# ottoesp_wrover.net
KiCad netlist of a schematic drawn in EAGLE
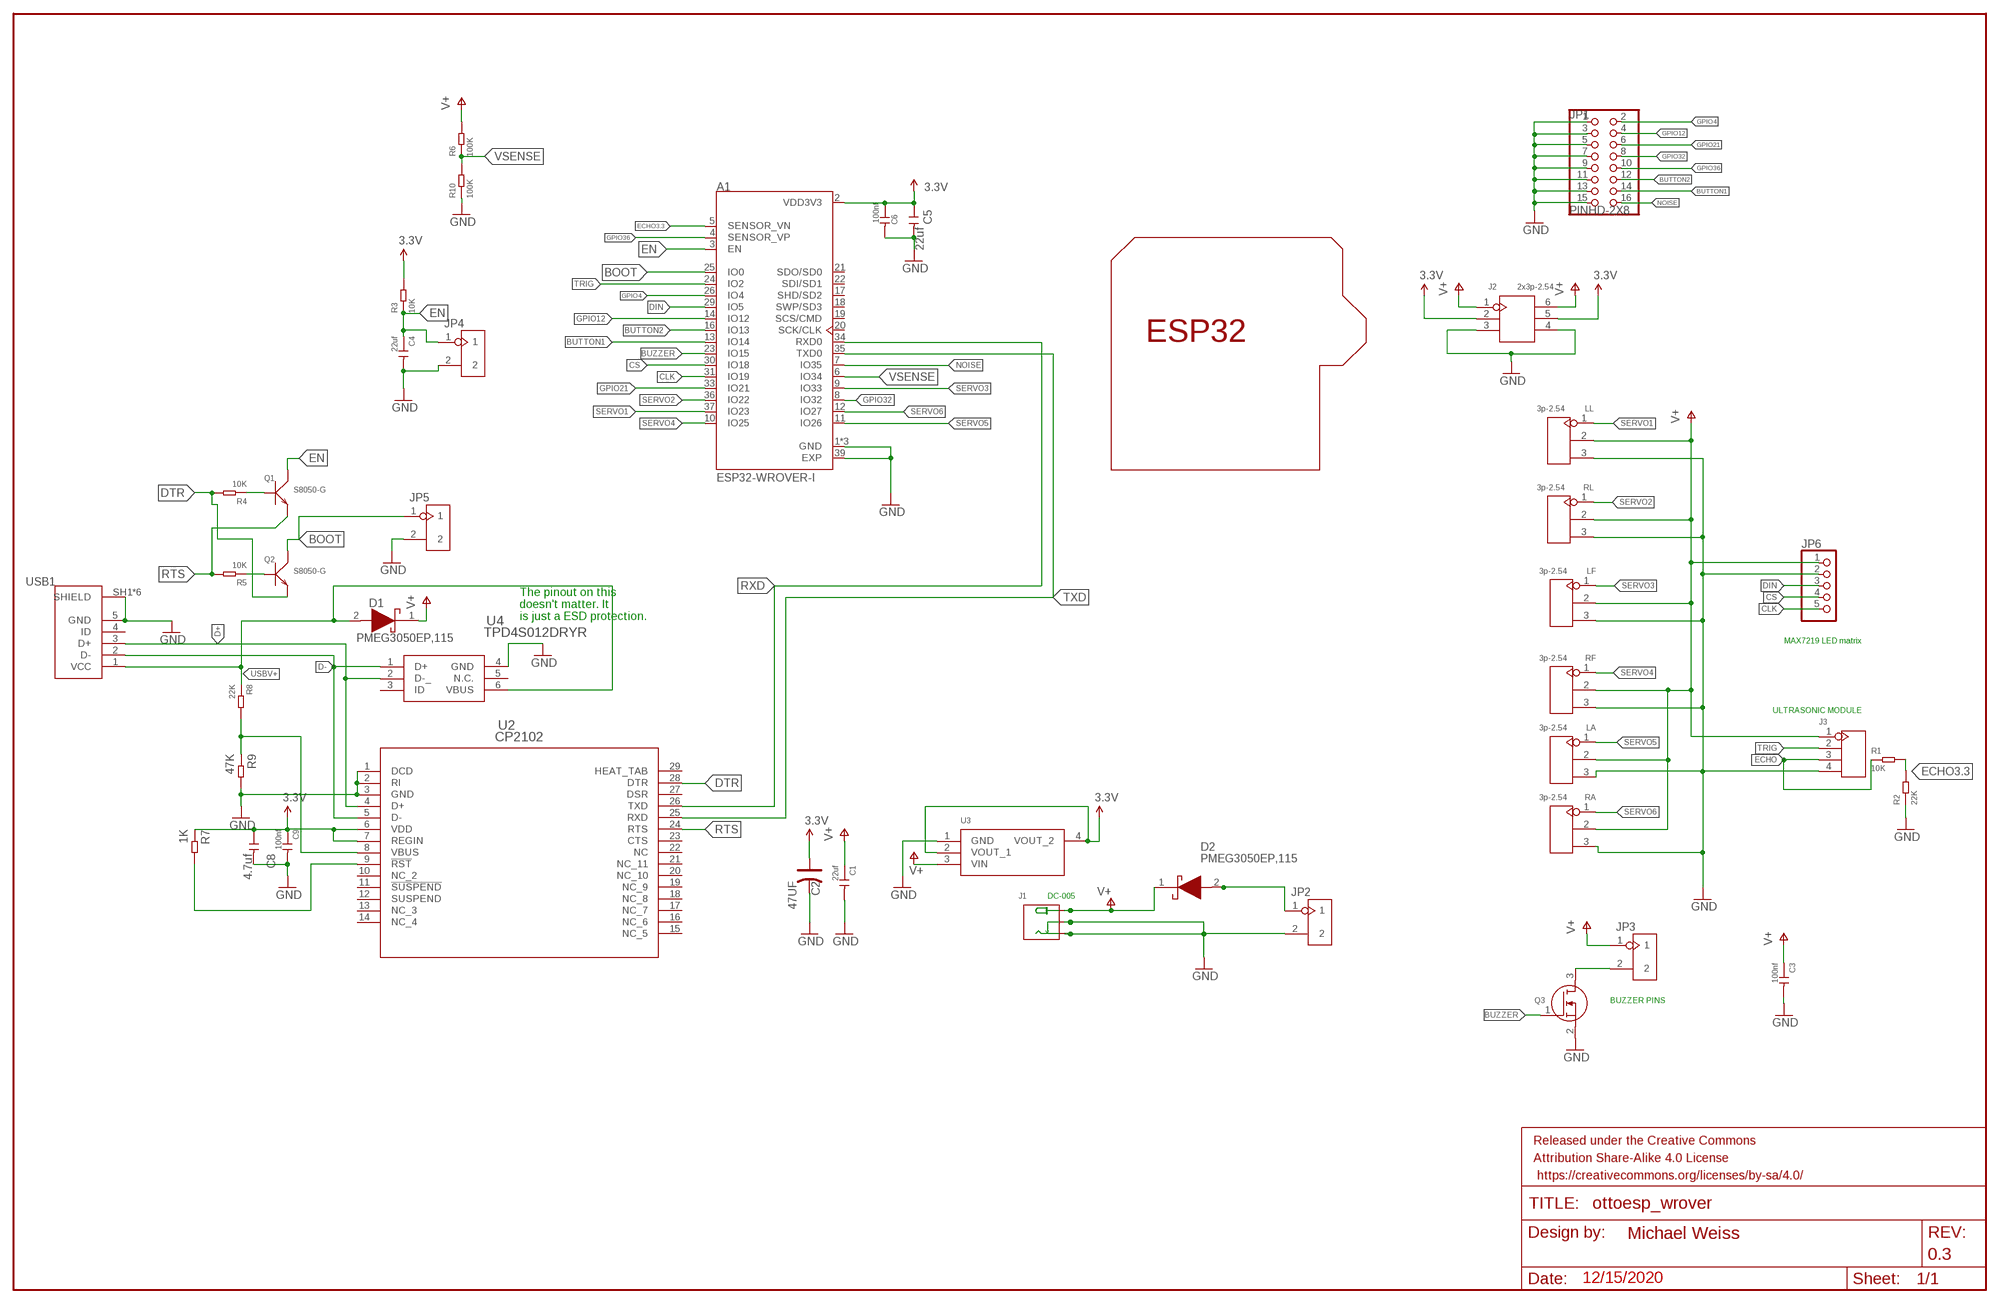
[diagram p0: schematic, sheet 1]

(export (version "E")
  (design (tool "Eeschema 10.0.6"))
  (components
    (comp (ref "A1")
      (value "ESP32-WROVER-I")
      (footprint "eagle-import:XCVR_ESP32-WROVER-I")
      (fields
        (field (name "MANUFACTURER_PART_NUMBER") "ESP32-WROVER-IE(M213EH2864UH3Q0) ")
        (field (name "MOUSER_PART_NUMBER") "356-ESP32WRVIE2864UC ")
      )
      (libsource (lib "eagle-import") (part "ESP32-WROVER-I"))
    )
    (comp (ref "C1")
      (value "22uf")
      (footprint "eagle-import:C0805")
      (fields
        (field (name "MANUFACTURER_PART_NUMBER") "C1206C226M9PACTU")
        (field (name "MOUSER_PART_NUMBER") "80-C1206C226M9P")
      )
      (libsource (lib "eagle-import") (part "CERAMIC-22UF-6.3V-20%-X5R(0805)"))
    )
    (comp (ref "C2")
      (value "47UF")
      (footprint "eagle-import:ELECTRO-SMD-C-6MM")
      (fields
        (field (name "MANUFACTURER_PART_NUMBER") " VE-470M1ETR-0605")
        (field (name "MOUSER_PART_NUMBER") "140-VE470M1ETR0605 ")
      )
      (libsource (lib "eagle-import") (part "ALUMINUM-SMD-47UF-25V(D6.3-H5.3MM)"))
    )
    (comp (ref "C3")
      (value "100nf")
      (footprint "eagle-import:C0805")
      (fields
        (field (name "MANUFACTURER_PART_NUMBER") "CC0805ZRY5V9BB104")
        (field (name "MOUSER_PART_NUMBER") "603-CC805ZRY5V9BB104")
      )
      (libsource (lib "eagle-import") (part "CERAMIC-100NF-50V-20%-X5R(0805)"))
    )
    (comp (ref "C4")
      (value "22uf")
      (footprint "eagle-import:C0805")
      (fields
        (field (name "MANUFACTURER_PART_NUMBER") "C1206C226M9PACTU")
        (field (name "MOUSER_PART_NUMBER") "80-C1206C226M9P")
      )
      (libsource (lib "eagle-import") (part "CERAMIC-22UF-6.3V-20%-X5R(0805)"))
    )
    (comp (ref "C5")
      (value "22uf")
      (footprint "eagle-import:C0805")
      (fields
        (field (name "MANUFACTURER_PART_NUMBER") "C1206C226M9PACTU")
        (field (name "MOUSER_PART_NUMBER") "80-C1206C226M9P")
      )
      (libsource (lib "eagle-import") (part "CERAMIC-22UF-6.3V-20%-X5R(0805)"))
    )
    (comp (ref "C6")
      (value "100nf")
      (footprint "eagle-import:C0805")
      (fields
        (field (name "MANUFACTURER_PART_NUMBER") "CC0805ZRY5V9BB104")
        (field (name "MOUSER_PART_NUMBER") "603-CC805ZRY5V9BB104")
      )
      (libsource (lib "eagle-import") (part "CERAMIC-100NF-50V-20%-X5R(0805)"))
    )
    (comp (ref "C8")
      (value "4.7uf")
      (footprint "eagle-import:C0805")
      (fields
        (field (name "MANUFACTURER_PART_NUMBER") "0805X475M250CT")
        (field (name "MOUSER_PART_NUMBER") "791-0805X475M250CT")
      )
      (libsource (lib "eagle-import") (part "CERAMIC-4.7UF-25V-10%-X5R(0805)"))
    )
    (comp (ref "C9")
      (value "100nf")
      (footprint "eagle-import:C0805")
      (fields
        (field (name "MANUFACTURER_PART_NUMBER") "CC0805ZRY5V9BB104")
        (field (name "MOUSER_PART_NUMBER") "603-CC805ZRY5V9BB104")
      )
      (libsource (lib "eagle-import") (part "CERAMIC-100NF-50V-20%-X5R(0805)"))
    )
    (comp (ref "D1")
      (value "PMEG3050EP,115")
      (footprint "eagle-import:PMEG3050EP115")
      (fields (field (name "MOUSER_PART_NUMBER") "771-PMEG3050EP115"))
      (libsource (lib "eagle-import") (part "PMEG3050EP,115"))
    )
    (comp (ref "D2")
      (value "PMEG3050EP,115")
      (footprint "eagle-import:PMEG3050EP115")
      (fields (field (name "MOUSER_PART_NUMBER") "771-PMEG3050EP115"))
      (libsource (lib "eagle-import") (part "PMEG3050EP,115"))
    )
    (comp (ref "FRAME1")
      (value "FRAME-LEDGERMISHAFARMS")
      (footprint "eagle-import:MISHAFARMS")
      (fields (field (name "DESIGNER") "Michael Weiss") (field (name "REV") "0.3"))
      (libsource (lib "eagle-import") (part "FRAME-LEDGERMISHAFARMS"))
    )
    (comp (ref "J1")
      (value "DC-005")
      (footprint "eagle-import:DCJ3P-14.2X11.0X9.0MM")
      (libsource (lib "eagle-import") (part "CONN-POWER-JACK-2.1MM(DC-005)"))
    )
    (comp (ref "J2")
      (value "2x3p-2.54")
      (footprint "eagle-import:H2X3-2.54")
      (fields (field (name "MANUFACTURER_PART_NUMBER") "P125-12A1BS116A1"))
      (libsource (lib "eagle-import") (part "DIP-BLACK-MALE-HEADER(2X3P-2.54）-2.54"))
    )
    (comp (ref "J3")
      (value "4p-2.54")
      (footprint "eagle-import:H4-2.54")
      (fields (field (name "MANUFACTURER_PART_NUMBER") "P125-1104A0BS116A1"))
      (libsource (lib "eagle-import") (part "DIP-BLACK-MALE-HEADER-VERT(4P-2.54)"))
    )
    (comp (ref "JP1")
      (value "PINHD-2X8")
      (footprint "eagle-import:2X08")
      (libsource (lib "eagle-import") (part "PINHD-2X8"))
    )
    (comp (ref "JP2")
      (value "2p-2.54")
      (footprint "eagle-import:H2-2.54")
      (fields (field (name "MANUFACTURER_PART_NUMBER") "P125-1102A0BS116A1"))
      (libsource (lib "eagle-import") (part "DIP-BLACK-MALE-HEADER-VERT(2P-2.54)"))
    )
    (comp (ref "JP3")
      (value "2p-2.54")
      (footprint "eagle-import:H2-2.54")
      (fields (field (name "MANUFACTURER_PART_NUMBER") "P125-1102A0BS116A1"))
      (libsource (lib "eagle-import") (part "DIP-BLACK-MALE-HEADER-VERT(2P-2.54)"))
    )
    (comp (ref "JP4")
      (value "2p-2.54")
      (footprint "eagle-import:H2-2.54")
      (fields (field (name "MANUFACTURER_PART_NUMBER") "P125-1102A0BS116A1"))
      (libsource (lib "eagle-import") (part "DIP-BLACK-MALE-HEADER-VERT(2P-2.54)"))
    )
    (comp (ref "JP5")
      (value "2p-2.54")
      (footprint "eagle-import:H2-2.54")
      (fields (field (name "MANUFACTURER_PART_NUMBER") "P125-1102A0BS116A1"))
      (libsource (lib "eagle-import") (part "DIP-BLACK-MALE-HEADER-VERT(2P-2.54)"))
    )
    (comp (ref "JP6")
      (value "PINHD-1X5")
      (footprint "eagle-import:1X05")
      (libsource (lib "eagle-import") (part "PINHD-1X5"))
    )
    (comp (ref "LA")
      (value "3p-2.54")
      (footprint "eagle-import:H3-2.54")
      (libsource (lib "eagle-import") (part "DIP-BLACK-MALE-HEADER-VERT(3P-2.54)"))
    )
    (comp (ref "LF")
      (value "3p-2.54")
      (footprint "eagle-import:H3-2.54")
      (libsource (lib "eagle-import") (part "DIP-BLACK-MALE-HEADER-VERT(3P-2.54)"))
    )
    (comp (ref "LL")
      (value "3p-2.54")
      (footprint "eagle-import:H3-2.54")
      (libsource (lib "eagle-import") (part "DIP-BLACK-MALE-HEADER-VERT(3P-2.54)"))
    )
    (comp (ref "Q1")
      (value "S8050-G")
      (footprint "eagle-import:SOT-23")
      (fields
        (field (name "MANUFACTURER_PART_NUMBER") "SS8050-G")
        (field (name "MOUSER_PART_NUMBER") "750-SS8050-G")
      )
      (libsource (lib "eagle-import") (part "SMD-TRANSISTORS-NPN-25V-500MW-S8050(SOT-23)"))
    )
    (comp (ref "Q2")
      (value "S8050-G")
      (footprint "eagle-import:SOT-23")
      (fields
        (field (name "MANUFACTURER_PART_NUMBER") "SS8050-G")
        (field (name "MOUSER_PART_NUMBER") "750-SS8050-G")
      )
      (libsource (lib "eagle-import") (part "SMD-TRANSISTORS-NPN-25V-500MW-S8050(SOT-23)"))
    )
    (comp (ref "Q3")
      (value "CJ2302")
      (footprint "eagle-import:SOT95P230X110-3N")
      (fields
        (field (name "MANUFACTURER_PART_NUMBER") "2N7002NXAKR")
        (field (name "MOUSER_PART_NUMBER") "771-2N7002NXAKR")
      )
      (libsource (lib "eagle-import") (part "2N7002NXAKR"))
    )
    (comp (ref "R1")
      (value "10K")
      (footprint "eagle-import:R0805")
      (fields
        (field (name "MANUFACTURER_PART_NUMBER") "RK73H2ATTD1002F ")
        (field (name "MOUSER_PART_NUMBER") "660-RK73H2ATTD1002F")
      )
      (libsource (lib "eagle-import") (part "SMD-RES-10K-1%-1/4W(0805)"))
    )
    (comp (ref "R2")
      (value "22K")
      (footprint "eagle-import:R0805")
      (fields
        (field (name "MANUFACTURER_PART_NUMBER") "RK73B2ATTD223J")
        (field (name "MOUSER_PART_NUMBER") "660-RK73B2ATTD223J")
      )
      (libsource (lib "eagle-import") (part "SMD-RES-22K-5%-1/4W(0805)"))
    )
    (comp (ref "R3")
      (value "10K")
      (footprint "eagle-import:R0805")
      (fields
        (field (name "MANUFACTURER_PART_NUMBER") "RK73H2ATTD1002F ")
        (field (name "MOUSER_PART_NUMBER") "660-RK73H2ATTD1002F")
      )
      (libsource (lib "eagle-import") (part "SMD-RES-10K-1%-1/4W(0805)"))
    )
    (comp (ref "R4")
      (value "10K")
      (footprint "eagle-import:R0805")
      (fields
        (field (name "MANUFACTURER_PART_NUMBER") "RK73H2ATTD1002F ")
        (field (name "MOUSER_PART_NUMBER") "660-RK73H2ATTD1002F")
      )
      (libsource (lib "eagle-import") (part "SMD-RES-10K-1%-1/4W(0805)"))
    )
    (comp (ref "R5")
      (value "10K")
      (footprint "eagle-import:R0805")
      (fields
        (field (name "MANUFACTURER_PART_NUMBER") "RK73H2ATTD1002F ")
        (field (name "MOUSER_PART_NUMBER") "660-RK73H2ATTD1002F")
      )
      (libsource (lib "eagle-import") (part "SMD-RES-10K-1%-1/4W(0805)"))
    )
    (comp (ref "R6")
      (value "100K")
      (footprint "eagle-import:R0805")
      (fields
        (field (name "MANUFACTURER_PART_NUMBER") "RR1220P-104-D")
        (field (name "MOUSER_PART_NUMBER") "754-RR1220P-104D")
      )
      (libsource (lib "eagle-import") (part "SMD-RES-100K-.5%-1/10W(0805)"))
    )
    (comp (ref "R7")
      (value "1K")
      (footprint "eagle-import:R0805")
      (fields
        (field (name "MANUFACTURER_PART_NUMBER") "CRCW08051K00FKEAC")
        (field (name "MOUSER_PART_NUMBER") "71-CRCW08051K00FKEAC")
      )
      (libsource (lib "eagle-import") (part "SMD-RES-1K-1%-1/8W(0805)"))
    )
    (comp (ref "R8")
      (value "22K")
      (footprint "eagle-import:R0805")
      (fields
        (field (name "MANUFACTURER_PART_NUMBER") "RK73B2ATTD223J")
        (field (name "MOUSER_PART_NUMBER") "660-RK73B2ATTD223J")
      )
      (libsource (lib "eagle-import") (part "SMD-RES-22K-5%-1/4W(0805)"))
    )
    (comp (ref "R9")
      (value "47K")
      (footprint "eagle-import:R0805")
      (fields
        (field (name "MANUFACTURER_PART_NUMBER") "RK73H2ATTD4702F")
        (field (name "MOUSER_PART_NUMBER") "660-RK73H2ATTD4702F")
      )
      (libsource (lib "eagle-import") (part "SMD-RES-47K-1%-1/4W(0805)"))
    )
    (comp (ref "R10")
      (value "100K")
      (footprint "eagle-import:R0805")
      (fields
        (field (name "MANUFACTURER_PART_NUMBER") "RR1220P-104-D")
        (field (name "MOUSER_PART_NUMBER") "754-RR1220P-104D")
      )
      (libsource (lib "eagle-import") (part "SMD-RES-100K-.5%-1/10W(0805)"))
    )
    (comp (ref "RA")
      (value "3p-2.54")
      (footprint "eagle-import:H3-2.54")
      (libsource (lib "eagle-import") (part "DIP-BLACK-MALE-HEADER-VERT(3P-2.54)"))
    )
    (comp (ref "RF")
      (value "3p-2.54")
      (footprint "eagle-import:H3-2.54")
      (libsource (lib "eagle-import") (part "DIP-BLACK-MALE-HEADER-VERT(3P-2.54)"))
    )
    (comp (ref "RL")
      (value "3p-2.54")
      (footprint "eagle-import:H3-2.54")
      (libsource (lib "eagle-import") (part "DIP-BLACK-MALE-HEADER-VERT(3P-2.54)"))
    )
    (comp (ref "U$2")
      (value "ESP32_SHIELDSMALL")
      (footprint "eagle-import:ESP32_ARDUINOSHIELDSMALL")
      (libsource (lib "eagle-import") (part "ESP32_SHIELDSMALL"))
    )
    (comp (ref "U2")
      (value "CP2102")
      (footprint "eagle-import:QFN28N5X5-0P5P")
      (fields
        (field (name "MANUFACTURER_PART_NUMBER") "CP2102N-A02-GQFN28R")
        (field (name "MOUSER_PART_NUMBER") "634-CP2102NA02QFN28R")
      )
      (libsource (lib "eagle-import") (part "CP2102"))
    )
    (comp (ref "U3")
      (value "CJA1117B-3.3-SOT89")
      (footprint "eagle-import:SOT230P700X180-4N")
      (fields
        (field (name "MANUFACTURER_PART_NUMBER") "AP2114H-3.3TRG1")
        (field (name "MOUSER_PART_NUMBER") "621-AP2114H-3.3TRG1")
      )
      (libsource (lib "eagle-import") (part "AP2114H-3.3TRG1"))
    )
    (comp (ref "U4")
      (value "TPD4S012DRYR")
      (footprint "eagle-import:TPD4S012DRYR")
      (fields (field (name "MOUSER_PART_NUMBER") "595-TPD4S012DRYR"))
      (libsource (lib "eagle-import") (part "TPD4S012DRYR"))
    )
    (comp (ref "USB1")
      (value "ZX62-B-5PA")
      (footprint "eagle-import:HRS_ZX62-B-5PA(33)")
      (fields
        (field (name "MANUFACTURER_PART_NUMBER") "ZX62-B-5PA(33)")
        (field (name "MOUSER_PART_NUMBER") "798-ZX62-B-5PA33")
      )
      (libsource (lib "eagle-import") (part "ZX62-B-5PA(33)"))
    )
  )
  (nets
    (net (code "1") (name "3.3V") (class "Default")
      (node (ref "A1") (pin "2") (pinfunction "VDD3V3_2") (pintype "power_in"))
      (node (ref "C2") (pin "+") (pinfunction "+_+") (pintype "passive"))
      (node (ref "C5") (pin "1") (pinfunction "1_1") (pintype "passive"))
      (node (ref "C6") (pin "1") (pinfunction "1_1") (pintype "passive"))
      (node (ref "C8") (pin "1") (pinfunction "1_1") (pintype "passive"))
      (node (ref "C9") (pin "1") (pinfunction "1_1") (pintype "passive"))
      (node (ref "J2") (pin "2") (pinfunction "2_2") (pintype "bidirectional"))
      (node (ref "J2") (pin "5") (pinfunction "5_5") (pintype "bidirectional"))
      (node (ref "R3") (pin "2") (pinfunction "2_2") (pintype "passive"))
      (node (ref "R7") (pin "1") (pinfunction "1_1") (pintype "passive"))
      (node (ref "U2") (pin "6") (pinfunction "VDD_6") (pintype "passive"))
      (node (ref "U2") (pin "7") (pinfunction "REGIN_7") (pintype "passive"))
      (node (ref "U3") (pin "2") (pinfunction "VOUT_1_2") (pintype "bidirectional"))
      (node (ref "U3") (pin "4") (pinfunction "VOUT_2_4") (pintype "bidirectional"))
    )
    (net (code "2") (name "BOOT") (class "Default")
      (node (ref "A1") (pin "25") (pinfunction "IO0_25") (pintype "bidirectional"))
      (node (ref "JP5") (pin "1") (pinfunction "1_1") (pintype "bidirectional"))
      (node (ref "Q2") (pin "3") (pinfunction "C_3") (pintype "passive"))
    )
    (net (code "3") (name "BUTTON1") (class "Default")
      (node (ref "A1") (pin "13") (pinfunction "IO14_13") (pintype "bidirectional"))
      (node (ref "JP1") (pin "14") (pinfunction "14_14") (pintype "passive"))
    )
    (net (code "4") (name "BUTTON2") (class "Default")
      (node (ref "A1") (pin "16") (pinfunction "IO13_16") (pintype "bidirectional"))
      (node (ref "JP1") (pin "12") (pinfunction "12_12") (pintype "passive"))
    )
    (net (code "5") (name "BUZZER") (class "Default")
      (node (ref "A1") (pin "23") (pinfunction "IO15_23") (pintype "bidirectional"))
      (node (ref "Q3") (pin "1") (pinfunction "G_1") (pintype "bidirectional"))
    )
    (net (code "6") (name "CLK") (class "Default")
      (node (ref "A1") (pin "31") (pinfunction "IO19_31") (pintype "bidirectional"))
      (node (ref "JP6") (pin "5") (pinfunction "5_5") (pintype "passive"))
    )
    (net (code "7") (name "CS") (class "Default")
      (node (ref "A1") (pin "30") (pinfunction "IO18_30") (pintype "bidirectional"))
      (node (ref "JP6") (pin "4") (pinfunction "4_4") (pintype "passive"))
    )
    (net (code "8") (name "D+") (class "Default")
      (node (ref "U2") (pin "4") (pinfunction "D+_4") (pintype "passive"))
      (node (ref "U4") (pin "2") (pinfunction "D-__2") (pintype "bidirectional"))
      (node (ref "USB1") (pin "3") (pinfunction "D+_3") (pintype "passive"))
    )
    (net (code "9") (name "D-") (class "Default")
      (node (ref "U2") (pin "5") (pinfunction "D-_5") (pintype "passive"))
      (node (ref "U4") (pin "1") (pinfunction "D+_1") (pintype "bidirectional"))
      (node (ref "USB1") (pin "2") (pinfunction "D-_2") (pintype "passive"))
    )
    (net (code "10") (name "DIN") (class "Default")
      (node (ref "A1") (pin "29") (pinfunction "IO5_29") (pintype "bidirectional"))
      (node (ref "JP6") (pin "3") (pinfunction "3_3") (pintype "passive"))
    )
    (net (code "11") (name "DTR") (class "Default")
      (node (ref "Q2") (pin "2") (pinfunction "E_2") (pintype "passive"))
      (node (ref "R4") (pin "2") (pinfunction "2_2") (pintype "passive"))
      (node (ref "U2") (pin "28") (pinfunction "DTR_28") (pintype "passive"))
    )
    (net (code "12") (name "ECHO") (class "Default")
      (node (ref "J3") (pin "3") (pinfunction "P$3_3") (pintype "bidirectional"))
      (node (ref "R1") (pin "1") (pinfunction "1_1") (pintype "passive"))
    )
    (net (code "13") (name "ECHO3.3") (class "Default")
      (node (ref "A1") (pin "5") (pinfunction "SENSOR_VN_5") (pintype "input"))
      (node (ref "R1") (pin "2") (pinfunction "2_2") (pintype "passive"))
      (node (ref "R2") (pin "2") (pinfunction "2_2") (pintype "passive"))
    )
    (net (code "14") (name "EN") (class "Default")
      (node (ref "A1") (pin "3") (pinfunction "EN_3") (pintype "input"))
      (node (ref "C4") (pin "1") (pinfunction "1_1") (pintype "passive"))
      (node (ref "JP4") (pin "1") (pinfunction "1_1") (pintype "bidirectional"))
      (node (ref "Q1") (pin "3") (pinfunction "C_3") (pintype "passive"))
      (node (ref "R3") (pin "1") (pinfunction "1_1") (pintype "passive"))
    )
    (net (code "15") (name "GND") (class "Default")
      (node (ref "A1") (pin "1") (pinfunction "GND_1") (pintype "power_in"))
      (node (ref "A1") (pin "15") (pinfunction "GND_15") (pintype "power_in"))
      (node (ref "A1") (pin "38") (pinfunction "GND_38") (pintype "power_in"))
      (node (ref "A1") (pin "39") (pinfunction "EXP_39") (pintype "power_in"))
      (node (ref "C1") (pin "2") (pinfunction "2_2") (pintype "passive"))
      (node (ref "C2") (pin "-") (pinfunction "-_-") (pintype "passive"))
      (node (ref "C3") (pin "2") (pinfunction "2_2") (pintype "passive"))
      (node (ref "C4") (pin "2") (pinfunction "2_2") (pintype "passive"))
      (node (ref "C5") (pin "2") (pinfunction "2_2") (pintype "passive"))
      (node (ref "C6") (pin "2") (pinfunction "2_2") (pintype "passive"))
      (node (ref "C8") (pin "2") (pinfunction "2_2") (pintype "passive"))
      (node (ref "C9") (pin "2") (pinfunction "2_2") (pintype "passive"))
      (node (ref "J1") (pin "-1B") (pinfunction "-_-1B") (pintype "bidirectional"))
      (node (ref "J1") (pin "-1T") (pinfunction "-_-1T") (pintype "bidirectional"))
      (node (ref "J1") (pin "-2") (pinfunction "CDN_-2") (pintype "bidirectional"))
      (node (ref "J1") (pin "-2B") (pinfunction "CDN_-2B") (pintype "bidirectional"))
      (node (ref "J2") (pin "3") (pinfunction "3_3") (pintype "bidirectional"))
      (node (ref "J2") (pin "4") (pinfunction "4_4") (pintype "bidirectional"))
      (node (ref "J3") (pin "4") (pinfunction "P$4_4") (pintype "bidirectional"))
      (node (ref "JP1") (pin "1") (pinfunction "1_1") (pintype "passive"))
      (node (ref "JP1") (pin "11") (pinfunction "11_11") (pintype "passive"))
      (node (ref "JP1") (pin "13") (pinfunction "13_13") (pintype "passive"))
      (node (ref "JP1") (pin "15") (pinfunction "15_15") (pintype "passive"))
      (node (ref "JP1") (pin "3") (pinfunction "3_3") (pintype "passive"))
      (node (ref "JP1") (pin "5") (pinfunction "5_5") (pintype "passive"))
      (node (ref "JP1") (pin "7") (pinfunction "7_7") (pintype "passive"))
      (node (ref "JP1") (pin "9") (pinfunction "9_9") (pintype "passive"))
      (node (ref "JP2") (pin "2") (pinfunction "2_2") (pintype "bidirectional"))
      (node (ref "JP4") (pin "2") (pinfunction "2_2") (pintype "bidirectional"))
      (node (ref "JP5") (pin "2") (pinfunction "2_2") (pintype "bidirectional"))
      (node (ref "JP6") (pin "2") (pinfunction "2_2") (pintype "passive"))
      (node (ref "LA") (pin "3") (pinfunction "P$3_3") (pintype "bidirectional"))
      (node (ref "LF") (pin "3") (pinfunction "P$3_3") (pintype "bidirectional"))
      (node (ref "LL") (pin "3") (pinfunction "P$3_3") (pintype "bidirectional"))
      (node (ref "Q3") (pin "2") (pinfunction "S_2") (pintype "bidirectional"))
      (node (ref "R10") (pin "1") (pinfunction "1_1") (pintype "passive"))
      (node (ref "R2") (pin "1") (pinfunction "1_1") (pintype "passive"))
      (node (ref "R9") (pin "2") (pinfunction "2_2") (pintype "passive"))
      (node (ref "RA") (pin "3") (pinfunction "P$3_3") (pintype "bidirectional"))
      (node (ref "RF") (pin "3") (pinfunction "P$3_3") (pintype "bidirectional"))
      (node (ref "RL") (pin "3") (pinfunction "P$3_3") (pintype "bidirectional"))
      (node (ref "U2") (pin "1") (pinfunction "DCD_1") (pintype "passive"))
      (node (ref "U2") (pin "2") (pinfunction "RI_2") (pintype "passive"))
      (node (ref "U2") (pin "3") (pinfunction "GND_3") (pintype "passive"))
      (node (ref "U3") (pin "1") (pinfunction "GND_1") (pintype "bidirectional"))
      (node (ref "U4") (pin "4") (pinfunction "GND_4") (pintype "bidirectional"))
      (node (ref "USB1") (pin "5") (pinfunction "GND_5") (pintype "passive"))
      (node (ref "USB1") (pin "SH1") (pinfunction "SHIELD_SH1") (pintype "passive"))
      (node (ref "USB1") (pin "SH2") (pinfunction "SHIELD_SH2") (pintype "passive"))
      (node (ref "USB1") (pin "SH3") (pinfunction "SHIELD_SH3") (pintype "passive"))
      (node (ref "USB1") (pin "SH4") (pinfunction "SHIELD_SH4") (pintype "passive"))
      (node (ref "USB1") (pin "SH5") (pinfunction "SHIELD_SH5") (pintype "passive"))
      (node (ref "USB1") (pin "SH6") (pinfunction "SHIELD_SH6") (pintype "passive"))
    )
    (net (code "16") (name "GPIO4") (class "Default")
      (node (ref "A1") (pin "26") (pinfunction "IO4_26") (pintype "bidirectional"))
      (node (ref "JP1") (pin "2") (pinfunction "2_2") (pintype "passive"))
    )
    (net (code "17") (name "GPIO12") (class "Default")
      (node (ref "A1") (pin "14") (pinfunction "IO12_14") (pintype "bidirectional"))
      (node (ref "JP1") (pin "4") (pinfunction "4_4") (pintype "passive"))
    )
    (net (code "18") (name "GPIO21") (class "Default")
      (node (ref "A1") (pin "33") (pinfunction "IO21_33") (pintype "bidirectional"))
      (node (ref "JP1") (pin "6") (pinfunction "6_6") (pintype "passive"))
    )
    (net (code "19") (name "GPIO32") (class "Default")
      (node (ref "A1") (pin "8") (pinfunction "IO32_8") (pintype "bidirectional"))
      (node (ref "JP1") (pin "8") (pinfunction "8_8") (pintype "passive"))
    )
    (net (code "20") (name "GPIO36") (class "Default")
      (node (ref "A1") (pin "4") (pinfunction "SENSOR_VP_4") (pintype "input"))
      (node (ref "JP1") (pin "10") (pinfunction "10_10") (pintype "passive"))
    )
    (net (code "21") (name "NOISE") (class "Default")
      (node (ref "A1") (pin "7") (pinfunction "IO35_7") (pintype "input"))
      (node (ref "JP1") (pin "16") (pinfunction "16_16") (pintype "passive"))
    )
    (net (code "22") (name "Net-(D2-A)") (class "Default")
      (node (ref "D2") (pin "2") (pinfunction "A_2") (pintype "bidirectional"))
      (node (ref "JP2") (pin "1") (pinfunction "1_1") (pintype "bidirectional"))
    )
    (net (code "23") (name "Net-(Q1-B)") (class "Default")
      (node (ref "Q1") (pin "1") (pinfunction "B_1") (pintype "passive"))
      (node (ref "R4") (pin "1") (pinfunction "1_1") (pintype "passive"))
    )
    (net (code "24") (name "Net-(Q2-B)") (class "Default")
      (node (ref "Q2") (pin "1") (pinfunction "B_1") (pintype "passive"))
      (node (ref "R5") (pin "1") (pinfunction "1_1") (pintype "passive"))
    )
    (net (code "25") (name "Net-(Q3-D)") (class "Default")
      (node (ref "JP3") (pin "2") (pinfunction "2_2") (pintype "bidirectional"))
      (node (ref "Q3") (pin "3") (pinfunction "D_3") (pintype "bidirectional"))
    )
    (net (code "26") (name "Net-(U2-VBUS)") (class "Default")
      (node (ref "R8") (pin "2") (pinfunction "2_2") (pintype "passive"))
      (node (ref "R9") (pin "1") (pinfunction "1_1") (pintype "passive"))
      (node (ref "U2") (pin "8") (pinfunction "VBUS_8") (pintype "passive"))
    )
    (net (code "27") (name "Net-(U2-~{RST})") (class "Default")
      (node (ref "R7") (pin "2") (pinfunction "2_2") (pintype "passive"))
      (node (ref "U2") (pin "9") (pinfunction "~{RST}_9") (pintype "passive"))
    )
    (net (code "28") (name "RTS") (class "Default")
      (node (ref "Q1") (pin "2") (pinfunction "E_2") (pintype "passive"))
      (node (ref "R5") (pin "2") (pinfunction "2_2") (pintype "passive"))
      (node (ref "U2") (pin "24") (pinfunction "RTS_24") (pintype "passive"))
    )
    (net (code "29") (name "RXD") (class "Default")
      (node (ref "A1") (pin "34") (pinfunction "RXD0_34") (pintype "bidirectional"))
      (node (ref "U2") (pin "26") (pinfunction "TXD_26") (pintype "passive"))
    )
    (net (code "30") (name "SERVO1") (class "Default")
      (node (ref "A1") (pin "37") (pinfunction "IO23_37") (pintype "bidirectional"))
      (node (ref "LL") (pin "1") (pinfunction "P$1_1") (pintype "bidirectional"))
    )
    (net (code "31") (name "SERVO2") (class "Default")
      (node (ref "A1") (pin "36") (pinfunction "IO22_36") (pintype "bidirectional"))
      (node (ref "RL") (pin "1") (pinfunction "P$1_1") (pintype "bidirectional"))
    )
    (net (code "32") (name "SERVO3") (class "Default")
      (node (ref "A1") (pin "9") (pinfunction "IO33_9") (pintype "bidirectional"))
      (node (ref "LF") (pin "1") (pinfunction "P$1_1") (pintype "bidirectional"))
    )
    (net (code "33") (name "SERVO4") (class "Default")
      (node (ref "A1") (pin "10") (pinfunction "IO25_10") (pintype "bidirectional"))
      (node (ref "RF") (pin "1") (pinfunction "P$1_1") (pintype "bidirectional"))
    )
    (net (code "34") (name "SERVO5") (class "Default")
      (node (ref "A1") (pin "11") (pinfunction "IO26_11") (pintype "bidirectional"))
      (node (ref "LA") (pin "1") (pinfunction "P$1_1") (pintype "bidirectional"))
    )
    (net (code "35") (name "SERVO6") (class "Default")
      (node (ref "A1") (pin "12") (pinfunction "IO27_12") (pintype "bidirectional"))
      (node (ref "RA") (pin "1") (pinfunction "P$1_1") (pintype "bidirectional"))
    )
    (net (code "36") (name "TRIG") (class "Default")
      (node (ref "A1") (pin "24") (pinfunction "IO2_24") (pintype "bidirectional"))
      (node (ref "J3") (pin "2") (pinfunction "P$2_2") (pintype "bidirectional"))
    )
    (net (code "37") (name "TXD") (class "Default")
      (node (ref "A1") (pin "35") (pinfunction "TXD0_35") (pintype "bidirectional"))
      (node (ref "U2") (pin "25") (pinfunction "RXD_25") (pintype "passive"))
    )
    (net (code "38") (name "USBV+") (class "Default")
      (node (ref "D1") (pin "2") (pinfunction "A_2") (pintype "bidirectional"))
      (node (ref "R8") (pin "1") (pinfunction "1_1") (pintype "passive"))
      (node (ref "U4") (pin "6") (pinfunction "VBUS_6") (pintype "bidirectional"))
      (node (ref "USB1") (pin "1") (pinfunction "VCC_1") (pintype "passive"))
    )
    (net (code "39") (name "V+") (class "Default")
      (node (ref "C1") (pin "1") (pinfunction "1_1") (pintype "passive"))
      (node (ref "C3") (pin "1") (pinfunction "1_1") (pintype "passive"))
      (node (ref "D1") (pin "1") (pinfunction "K_1") (pintype "bidirectional"))
      (node (ref "D2") (pin "1") (pinfunction "K_1") (pintype "bidirectional"))
      (node (ref "J1") (pin "+B") (pinfunction "+_+B") (pintype "bidirectional"))
      (node (ref "J1") (pin "+T") (pinfunction "+_+T") (pintype "bidirectional"))
      (node (ref "J2") (pin "1") (pinfunction "1_1") (pintype "bidirectional"))
      (node (ref "J2") (pin "6") (pinfunction "6_6") (pintype "bidirectional"))
      (node (ref "J3") (pin "1") (pinfunction "P$1_1") (pintype "bidirectional"))
      (node (ref "JP3") (pin "1") (pinfunction "1_1") (pintype "bidirectional"))
      (node (ref "JP6") (pin "1") (pinfunction "1_1") (pintype "passive"))
      (node (ref "LA") (pin "2") (pinfunction "P$2_2") (pintype "bidirectional"))
      (node (ref "LF") (pin "2") (pinfunction "P$2_2") (pintype "bidirectional"))
      (node (ref "LL") (pin "2") (pinfunction "P$2_2") (pintype "bidirectional"))
      (node (ref "R6") (pin "2") (pinfunction "2_2") (pintype "passive"))
      (node (ref "RA") (pin "2") (pinfunction "P$2_2") (pintype "bidirectional"))
      (node (ref "RF") (pin "2") (pinfunction "P$2_2") (pintype "bidirectional"))
      (node (ref "RL") (pin "2") (pinfunction "P$2_2") (pintype "bidirectional"))
      (node (ref "U3") (pin "3") (pinfunction "VIN_3") (pintype "bidirectional"))
    )
    (net (code "40") (name "VSENSE") (class "Default")
      (node (ref "A1") (pin "6") (pinfunction "IO34_6") (pintype "input"))
      (node (ref "R10") (pin "2") (pinfunction "2_2") (pintype "passive"))
      (node (ref "R6") (pin "1") (pinfunction "1_1") (pintype "passive"))
    )
    (net (code "41") (name "unconnected-(A1-SCK{slash}CLK-Pad20)") (class "Default")
      (node (ref "A1") (pin "20") (pinfunction "SCK/CLK_20") (pintype "bidirectional"))
    )
    (net (code "42") (name "unconnected-(A1-SCS{slash}CMD-Pad19)") (class "Default")
      (node (ref "A1") (pin "19") (pinfunction "SCS/CMD_19") (pintype "bidirectional"))
    )
    (net (code "43") (name "unconnected-(A1-SDI{slash}SD1-Pad22)") (class "Default")
      (node (ref "A1") (pin "22") (pinfunction "SDI/SD1_22") (pintype "bidirectional"))
    )
    (net (code "44") (name "unconnected-(A1-SDO{slash}SD0-Pad21)") (class "Default")
      (node (ref "A1") (pin "21") (pinfunction "SDO/SD0_21") (pintype "bidirectional"))
    )
    (net (code "45") (name "unconnected-(A1-SHD{slash}SD2-Pad17)") (class "Default")
      (node (ref "A1") (pin "17") (pinfunction "SHD/SD2_17") (pintype "bidirectional"))
    )
    (net (code "46") (name "unconnected-(A1-SWP{slash}SD3-Pad18)") (class "Default")
      (node (ref "A1") (pin "18") (pinfunction "SWP/SD3_18") (pintype "bidirectional"))
    )
    (net (code "47") (name "unconnected-(U2-CTS-Pad23)") (class "Default")
      (node (ref "U2") (pin "23") (pinfunction "CTS_23") (pintype "passive"))
    )
    (net (code "48") (name "unconnected-(U2-DSR-Pad27)") (class "Default")
      (node (ref "U2") (pin "27") (pinfunction "DSR_27") (pintype "passive"))
    )
    (net (code "49") (name "unconnected-(U2-HEAT_TAB-Pad29)") (class "Default")
      (node (ref "U2") (pin "29") (pinfunction "HEAT_TAB_29") (pintype "passive"))
    )
    (net (code "50") (name "unconnected-(U2-NC-Pad22)") (class "Default")
      (node (ref "U2") (pin "22") (pinfunction "NC_22") (pintype "passive"))
    )
    (net (code "51") (name "unconnected-(U2-NC_2-Pad10)") (class "Default")
      (node (ref "U2") (pin "10") (pinfunction "NC_2_10") (pintype "passive"))
    )
    (net (code "52") (name "unconnected-(U2-NC_3-Pad13)") (class "Default")
      (node (ref "U2") (pin "13") (pinfunction "NC_3_13") (pintype "passive"))
    )
    (net (code "53") (name "unconnected-(U2-NC_4-Pad14)") (class "Default")
      (node (ref "U2") (pin "14") (pinfunction "NC_4_14") (pintype "passive"))
    )
    (net (code "54") (name "unconnected-(U2-NC_5-Pad15)") (class "Default")
      (node (ref "U2") (pin "15") (pinfunction "NC_5_15") (pintype "passive"))
    )
    (net (code "55") (name "unconnected-(U2-NC_6-Pad16)") (class "Default")
      (node (ref "U2") (pin "16") (pinfunction "NC_6_16") (pintype "passive"))
    )
    (net (code "56") (name "unconnected-(U2-NC_7-Pad17)") (class "Default")
      (node (ref "U2") (pin "17") (pinfunction "NC_7_17") (pintype "passive"))
    )
    (net (code "57") (name "unconnected-(U2-NC_8-Pad18)") (class "Default")
      (node (ref "U2") (pin "18") (pinfunction "NC_8_18") (pintype "passive"))
    )
    (net (code "58") (name "unconnected-(U2-NC_9-Pad19)") (class "Default")
      (node (ref "U2") (pin "19") (pinfunction "NC_9_19") (pintype "passive"))
    )
    (net (code "59") (name "unconnected-(U2-NC_10-Pad20)") (class "Default")
      (node (ref "U2") (pin "20") (pinfunction "NC_10_20") (pintype "passive"))
    )
    (net (code "60") (name "unconnected-(U2-NC_11-Pad21)") (class "Default")
      (node (ref "U2") (pin "21") (pinfunction "NC_11_21") (pintype "passive"))
    )
    (net (code "61") (name "unconnected-(U2-SUSPEND-Pad12)") (class "Default")
      (node (ref "U2") (pin "12") (pinfunction "SUSPEND_12") (pintype "passive"))
    )
    (net (code "62") (name "unconnected-(U2-~{SUSPEND}-Pad11)") (class "Default")
      (node (ref "U2") (pin "11") (pinfunction "~{SUSPEND}_11") (pintype "passive"))
    )
    (net (code "63") (name "unconnected-(U4-ID-Pad3)") (class "Default")
      (node (ref "U4") (pin "3") (pinfunction "ID_3") (pintype "bidirectional"))
    )
    (net (code "64") (name "unconnected-(U4-N.C.-Pad5)") (class "Default")
      (node (ref "U4") (pin "5") (pinfunction "N.C._5") (pintype "no_connect"))
    )
    (net (code "65") (name "unconnected-(USB1-ID-Pad4)") (class "Default")
      (node (ref "USB1") (pin "4") (pinfunction "ID_4") (pintype "passive"))
    )
  )
)
